# Power.net
KiCad netlist of a schematic drawn in Altium Designer
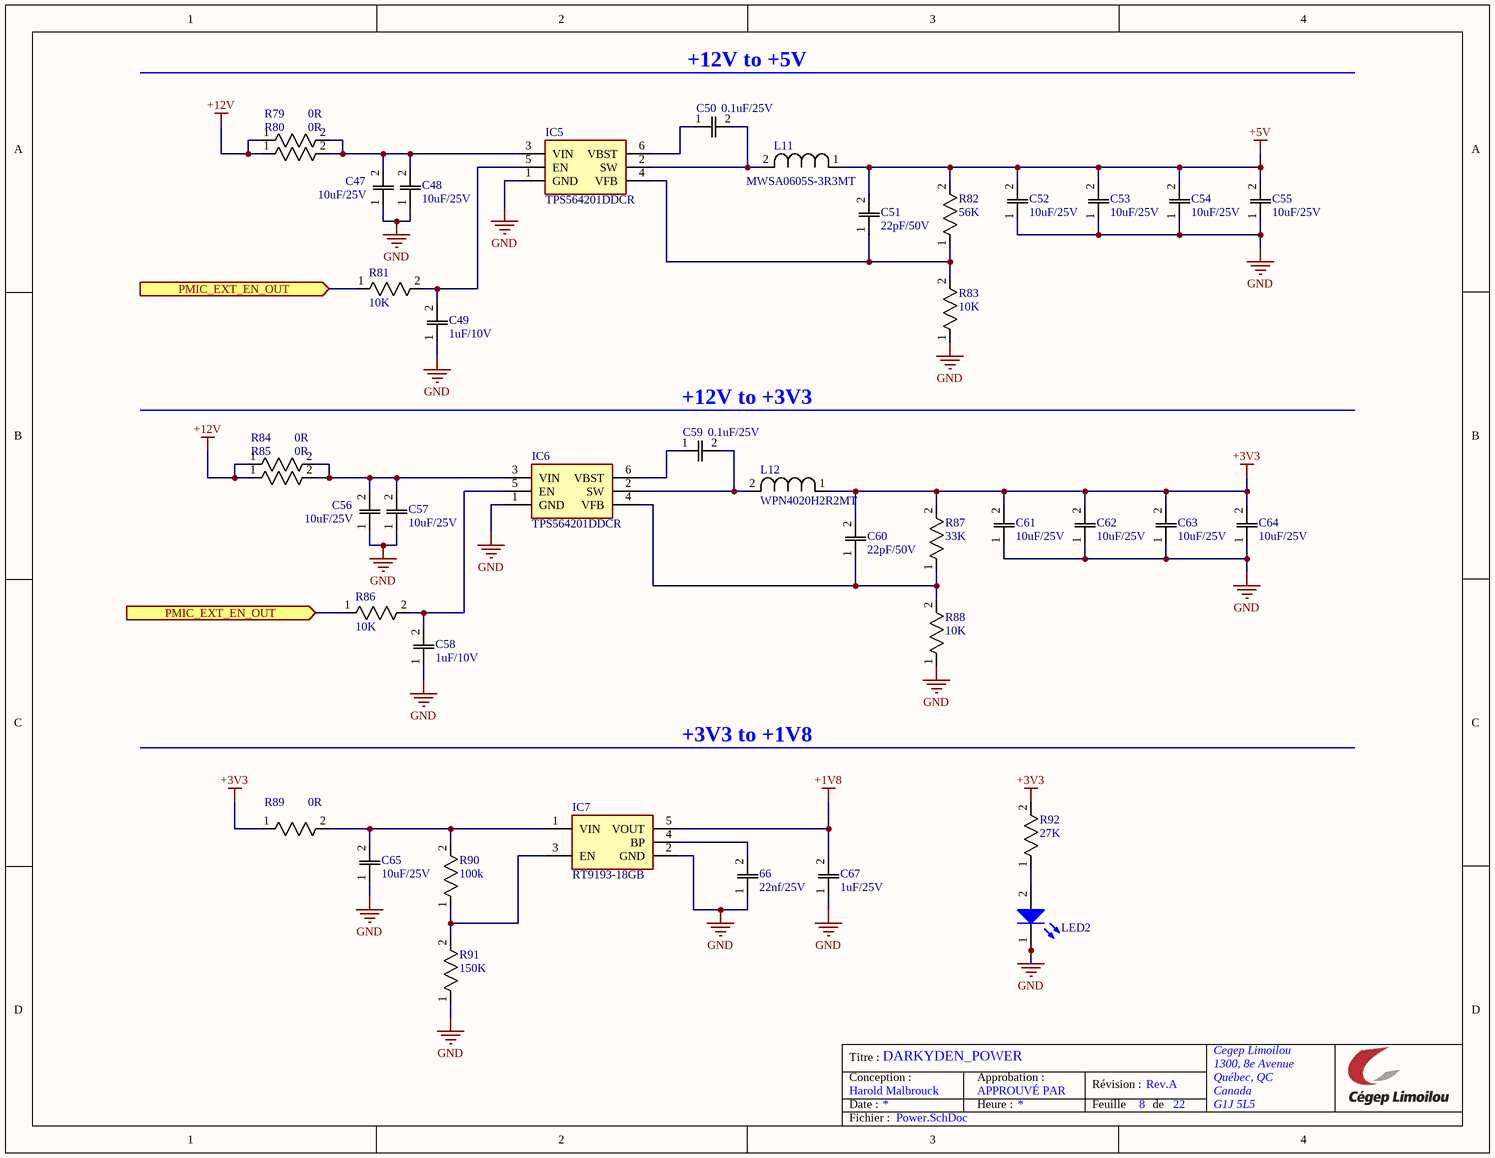
[diagram p0: Power.SchDoc]

(export (version "E")
  (design (tool "Eeschema 10.0.6"))
  (components
    (comp (ref "66")
      (value "22nf/25V")
      (footprint "SamacSys:C0805")
      (description "22nF, 25 V, 0805 [2012 Metric], 5%, C0G / NP0")
      (fields
        (field (name "MANUFACTURER_PART_NUMBER") "C0805C223J3GACTU")
        (field (name "MANUFACTURER") "KEMET")
      )
      (libsource (lib "SamacSys") (part "C0805C223J3GACTU"))
    )
    (comp (ref "C47")
      (value "10uF/25V")
      (footprint "CAPC220145_88N_KEM")
      (description "10uF / 25 VDC, +85degC, X5R Dielec, +/-10% ¦ KEMET C0805C106K3PACTU 0805")
      (fields
        (field (name "MANUFACTURER") "KEMET")
        (field (name "MANUFACTURER PART NUMBER") "C0805C106K3PACTU")
      )
      (libsource (lib "C0805C106K3PACTU") (part "C0805C106K3PACTU"))
    )
    (comp (ref "C48")
      (value "10uF/25V")
      (footprint "CAPC220145_88N_KEM")
      (description "10uF / 25 VDC, +85degC, X5R Dielec, +/-10% ¦ KEMET C0805C106K3PACTU 0805")
      (fields
        (field (name "MANUFACTURER") "KEMET")
        (field (name "MANUFACTURER PART NUMBER") "C0805C106K3PACTU")
      )
      (libsource (lib "C0805C106K3PACTU") (part "C0805C106K3PACTU"))
    )
    (comp (ref "C49")
      (value "1uF/10V")
      (footprint "CAPC220145_88N_KEM")
      (description "Multilayer Ceramic Capacitors MLCC - SMD/SMT 10V 1uF X7R 0805 10%")
      (fields
        (field (name "MANUFACTURER") "KEMET")
        (field (name "MANUFACTURER PART NUMBER") "C0805C105K8RACTU")
      )
      (libsource (lib "C0805C105K8RACTU") (part "C0805C105K8RACTU"))
    )
    (comp (ref "C50")
      (value "0.1uF/25V")
      (footprint "CAPC220145_88N_KEM")
      (description "0.1uF 25V X7R 10% SMD 0805 125C Plastic T/R")
      (fields
        (field (name "MANUFACTURER") "KEMET")
        (field (name "MANUFACTURER PART NUMBER") "C0805C104K3RACTU")
      )
      (libsource (lib "C0805C104K3RACTU") (part "C0805C104K3RACTU"))
    )
    (comp (ref "C51")
      (value "22pF/50V")
      (footprint "CAPC220145_88N_KEM")
      (description "Cap Ceramic 22pF 50V X7R 5% Pad SMD 0805 125°C T/R")
      (fields
        (field (name "MANUFACTURER") "KEMET")
        (field (name "MANUFACTURER PART NUMBER") "C0805C220J5RACTU")
      )
      (libsource (lib "C0805C220J5RACTU") (part "C0805C220J5RACTU"))
    )
    (comp (ref "C52")
      (value "10uF/25V")
      (footprint "CAPC220145_88N_KEM")
      (description "10uF / 25 VDC, +85degC, X5R Dielec, +/-10% ¦ KEMET C0805C106K3PACTU 0805")
      (fields
        (field (name "MANUFACTURER") "KEMET")
        (field (name "MANUFACTURER PART NUMBER") "C0805C106K3PACTU")
      )
      (libsource (lib "C0805C106K3PACTU") (part "C0805C106K3PACTU"))
    )
    (comp (ref "C53")
      (value "10uF/25V")
      (footprint "CAPC220145_88N_KEM")
      (description "10uF / 25 VDC, +85degC, X5R Dielec, +/-10% ¦ KEMET C0805C106K3PACTU 0805")
      (fields
        (field (name "MANUFACTURER") "KEMET")
        (field (name "MANUFACTURER PART NUMBER") "C0805C106K3PACTU")
      )
      (libsource (lib "C0805C106K3PACTU") (part "C0805C106K3PACTU"))
    )
    (comp (ref "C54")
      (value "10uF/25V")
      (footprint "CAPC220145_88N_KEM")
      (description "10uF / 25 VDC, +85degC, X5R Dielec, +/-10% ¦ KEMET C0805C106K3PACTU 0805")
      (fields
        (field (name "MANUFACTURER") "KEMET")
        (field (name "MANUFACTURER PART NUMBER") "C0805C106K3PACTU")
      )
      (libsource (lib "C0805C106K3PACTU") (part "C0805C106K3PACTU"))
    )
    (comp (ref "C55")
      (value "10uF/25V")
      (footprint "CAPC220145_88N_KEM")
      (description "10uF / 25 VDC, +85degC, X5R Dielec, +/-10% ¦ KEMET C0805C106K3PACTU 0805")
      (fields
        (field (name "MANUFACTURER") "KEMET")
        (field (name "MANUFACTURER PART NUMBER") "C0805C106K3PACTU")
      )
      (libsource (lib "C0805C106K3PACTU") (part "C0805C106K3PACTU"))
    )
    (comp (ref "C56")
      (value "10uF/25V")
      (footprint "CAPC220145_88N_KEM")
      (description "10uF / 25 VDC, +85degC, X5R Dielec, +/-10% ¦ KEMET C0805C106K3PACTU 0805")
      (fields
        (field (name "MANUFACTURER") "KEMET")
        (field (name "MANUFACTURER PART NUMBER") "C0805C106K3PACTU")
      )
      (libsource (lib "C0805C106K3PACTU") (part "C0805C106K3PACTU"))
    )
    (comp (ref "C57")
      (value "10uF/25V")
      (footprint "CAPC220145_88N_KEM")
      (description "10uF / 25 VDC, +85degC, X5R Dielec, +/-10% ¦ KEMET C0805C106K3PACTU 0805")
      (fields
        (field (name "MANUFACTURER") "KEMET")
        (field (name "MANUFACTURER PART NUMBER") "C0805C106K3PACTU")
      )
      (libsource (lib "C0805C106K3PACTU") (part "C0805C106K3PACTU"))
    )
    (comp (ref "C58")
      (value "1uF/10V")
      (footprint "CAPC220145_88N_KEM")
      (description "Multilayer Ceramic Capacitors MLCC - SMD/SMT 10V 1uF X7R 0805 10%")
      (fields
        (field (name "MANUFACTURER") "KEMET")
        (field (name "MANUFACTURER PART NUMBER") "C0805C105K8RACTU")
      )
      (libsource (lib "C0805C105K8RACTU") (part "C0805C105K8RACTU"))
    )
    (comp (ref "C59")
      (value "0.1uF/25V")
      (footprint "CAPC220145_88N_KEM")
      (description "0.1uF 25V X7R 10% SMD 0805 125C Plastic T/R")
      (fields
        (field (name "MANUFACTURER") "KEMET")
        (field (name "MANUFACTURER PART NUMBER") "C0805C104K3RACTU")
      )
      (libsource (lib "C0805C104K3RACTU") (part "C0805C104K3RACTU"))
    )
    (comp (ref "C60")
      (value "22pF/50V")
      (footprint "CAPC220145_88N_KEM")
      (description "Cap Ceramic 22pF 50V X7R 5% Pad SMD 0805 125°C T/R")
      (fields
        (field (name "MANUFACTURER") "KEMET")
        (field (name "MANUFACTURER PART NUMBER") "C0805C220J5RACTU")
      )
      (libsource (lib "C0805C220J5RACTU") (part "C0805C220J5RACTU"))
    )
    (comp (ref "C61")
      (value "10uF/25V")
      (footprint "CAPC220145_88N_KEM")
      (description "10uF / 25 VDC, +85degC, X5R Dielec, +/-10% ¦ KEMET C0805C106K3PACTU 0805")
      (fields
        (field (name "MANUFACTURER") "KEMET")
        (field (name "MANUFACTURER PART NUMBER") "C0805C106K3PACTU")
      )
      (libsource (lib "C0805C106K3PACTU") (part "C0805C106K3PACTU"))
    )
    (comp (ref "C62")
      (value "10uF/25V")
      (footprint "CAPC220145_88N_KEM")
      (description "10uF / 25 VDC, +85degC, X5R Dielec, +/-10% ¦ KEMET C0805C106K3PACTU 0805")
      (fields
        (field (name "MANUFACTURER") "KEMET")
        (field (name "MANUFACTURER PART NUMBER") "C0805C106K3PACTU")
      )
      (libsource (lib "C0805C106K3PACTU") (part "C0805C106K3PACTU"))
    )
    (comp (ref "C63")
      (value "10uF/25V")
      (footprint "CAPC220145_88N_KEM")
      (description "10uF / 25 VDC, +85degC, X5R Dielec, +/-10% ¦ KEMET C0805C106K3PACTU 0805")
      (fields
        (field (name "MANUFACTURER") "KEMET")
        (field (name "MANUFACTURER PART NUMBER") "C0805C106K3PACTU")
      )
      (libsource (lib "C0805C106K3PACTU") (part "C0805C106K3PACTU"))
    )
    (comp (ref "C64")
      (value "10uF/25V")
      (footprint "CAPC220145_88N_KEM")
      (description "10uF / 25 VDC, +85degC, X5R Dielec, +/-10% ¦ KEMET C0805C106K3PACTU 0805")
      (fields
        (field (name "MANUFACTURER") "KEMET")
        (field (name "MANUFACTURER PART NUMBER") "C0805C106K3PACTU")
      )
      (libsource (lib "C0805C106K3PACTU") (part "C0805C106K3PACTU"))
    )
    (comp (ref "C65")
      (value "10uF/25V")
      (footprint "CAPC220145_88N_KEM")
      (description "10uF / 25 VDC, +85degC, X5R Dielec, +/-10% ¦ KEMET C0805C106K3PACTU 0805")
      (fields
        (field (name "MANUFACTURER") "KEMET")
        (field (name "MANUFACTURER PART NUMBER") "C0805C106K3PACTU")
      )
      (libsource (lib "C0805C106K3PACTU") (part "C0805C106K3PACTU"))
    )
    (comp (ref "C67")
      (value "1uF/25V")
      (footprint "SamacSys:C0805")
      (description "1 µF, 25 V (DC), ±10 %, SMD 0805, X7R, C0805C105K3RAC7800")
      (fields
        (field (name "MANUFACTURER_PART_NUMBER") "C0805C105K3RACTU")
        (field (name "MOUSER PART NUMBER") "80-C0805C105K3R")
      )
      (libsource (lib "SamacSys") (part "C0805C105K3RACTU"))
    )
    (comp (ref "IC5")
      (value "TPS564201DDCR")
      (footprint "SamacSys:SOT95P280X110-6N")
      (fields
        (field (name "MOUSER PART NUMBER") "595-TPS564201DDCR")
        (field (name "MANUFACTURER") "Texas Instruments")
      )
      (libsource (lib "SamacSys") (part "TPS564201DDCR"))
    )
    (comp (ref "IC6")
      (value "TPS564201DDCR")
      (footprint "SamacSys:SOT95P280X110-6N")
      (fields
        (field (name "MOUSER PART NUMBER") "595-TPS564201DDCR")
        (field (name "MANUFACTURER") "Texas Instruments")
      )
      (libsource (lib "SamacSys") (part "TPS564201DDCR"))
    )
    (comp (ref "IC7")
      (value "RT9193-18GB")
      (footprint "SamacSys:SOT94P279X130-5N")
      (description "Linear Voltage Regulator IC Positive Fixed 1.8V Output 300mA SOT-23-5")
      (fields (field (name "MOUSER PART NUMBER") "835-RT9193-18GB"))
      (libsource (lib "SamacSys") (part "RT9193-18GB"))
    )
    (comp (ref "L11")
      (value "MWSA0605S-3R3MT")
      (footprint "IND_MWSA0603S_SNL")
      (description "3.3 µH Shielded Drum Core, Wirewound Inductor 8.5 A 22mOhm Max Nonstandard")
      (libsource (lib "MWSA0603S-XRXMT") (part "MWSA0605S-3R3MT"))
    )
    (comp (ref "L12")
      (value "WPN4020H2R2MT")
      (footprint "IND_WPN4020H_SNL")
      (description "2.2 µH Shielded Drum Core, Wirewound Inductor 4.3 A 48mOhm Max Nonstandard")
      (fields (field (name "MANUFACTURER") "Sunlord"))
      (libsource (lib "WPN4020H2R2MT") (part "WPN4020H2R2MT"))
    )
    (comp (ref "LED2")
      (value "Blue, 3.2V, 140°")
      (footprint "WL-SMCD_0603")
      (description "WL-SMCD Mono-color Chip LED Diffused, SMT, size 0603, Blue, 3.2V, 140°")
      (fields
        (field (name "MANUFACTURER PART NUMBER") "150060BS55040")
        (field (name "MANUFACTURER") "Wurth Elektronik")
      )
      (libsource (lib "0603_LED") (part "BLUE"))
    )
    (comp (ref "R79")
      (value "0R")
      (footprint "SamacSys:ERJ3EKF1000V")
      (description "Zero Ohm Resistor, Jumper, 0603 [1608 Metric], Thick Film, 100 mW, 1 A, Surface Mount")
      (fields
        (field (name "MANUFACTURER_PART_NUMBER") "ERJ-3GEY0R00V")
        (field (name "MOUSER PART NUMBER") "667-ERJ-3GEY0R00V")
      )
      (libsource (lib "SamacSys") (part "ERJ-3GEY0R00V"))
    )
    (comp (ref "R80")
      (value "0R")
      (footprint "SamacSys:ERJ3EKF1000V")
      (description "Zero Ohm Resistor, Jumper, 0603 [1608 Metric], Thick Film, 100 mW, 1 A, Surface Mount")
      (fields
        (field (name "MANUFACTURER_PART_NUMBER") "ERJ-3GEY0R00V")
        (field (name "MOUSER PART NUMBER") "667-ERJ-3GEY0R00V")
      )
      (libsource (lib "SamacSys") (part "ERJ-3GEY0R00V"))
    )
    (comp (ref "R81")
      (value "10K")
      (footprint "SamacSys:ERJ3EKF1000V")
      (description "10K Ohm 5% Res Thick Film 0603  0.1W(1/10W) ±200ppm/C Pad SMD Automotive T/R")
      (fields
        (field (name "MANUFACTURER_PART_NUMBER") "ERJ-3GEYJ103V")
        (field (name "MOUSER PART NUMBER") "667-ERJ-3GEYJ103V")
      )
      (libsource (lib "SamacSys") (part "ERJ-3GEYJ103V"))
    )
    (comp (ref "R82")
      (value "56K")
      (footprint "SamacSys:RESC1608X55N")
      (description "56K Ohm 1% 1/10W +/-100ppm/ßC Molded SMD Punched Carrier T/R")
      (fields
        (field (name "MANUFACTURER_PART_NUMBER") "ERJ-3EKF5602V")
        (field (name "MOUSER PART NUMBER") "667-ERJ-3EKF5602V")
      )
      (libsource (lib "SamacSys") (part "ERJ-3EKF5602V"))
    )
    (comp (ref "R83")
      (value "10K")
      (footprint "SamacSys:ERJ3EKF1000V")
      (description "10K Ohm 5% Res Thick Film 0603  0.1W(1/10W) ±200ppm/C Pad SMD Automotive T/R")
      (fields
        (field (name "MANUFACTURER_PART_NUMBER") "ERJ-3GEYJ103V")
        (field (name "MOUSER PART NUMBER") "667-ERJ-3GEYJ103V")
      )
      (libsource (lib "SamacSys") (part "ERJ-3GEYJ103V"))
    )
    (comp (ref "R84")
      (value "0R")
      (footprint "SamacSys:ERJ3EKF1000V")
      (description "Zero Ohm Resistor, Jumper, 0603 [1608 Metric], Thick Film, 100 mW, 1 A, Surface Mount")
      (fields
        (field (name "MANUFACTURER_PART_NUMBER") "ERJ-3GEY0R00V")
        (field (name "MOUSER PART NUMBER") "667-ERJ-3GEY0R00V")
      )
      (libsource (lib "SamacSys") (part "ERJ-3GEY0R00V"))
    )
    (comp (ref "R85")
      (value "0R")
      (footprint "SamacSys:ERJ3EKF1000V")
      (description "Zero Ohm Resistor, Jumper, 0603 [1608 Metric], Thick Film, 100 mW, 1 A, Surface Mount")
      (fields
        (field (name "MANUFACTURER_PART_NUMBER") "ERJ-3GEY0R00V")
        (field (name "MOUSER PART NUMBER") "667-ERJ-3GEY0R00V")
      )
      (libsource (lib "SamacSys") (part "ERJ-3GEY0R00V"))
    )
    (comp (ref "R86")
      (value "10K")
      (footprint "SamacSys:ERJ3EKF1000V")
      (description "10K Ohm 5% Res Thick Film 0603  0.1W(1/10W) ±200ppm/C Pad SMD Automotive T/R")
      (fields
        (field (name "MANUFACTURER_PART_NUMBER") "ERJ-3GEYJ103V")
        (field (name "MOUSER PART NUMBER") "667-ERJ-3GEYJ103V")
      )
      (libsource (lib "SamacSys") (part "ERJ-3GEYJ103V"))
    )
    (comp (ref "R87")
      (value "33K")
      (footprint "SamacSys:ERJ3EKF1000V")
      (description "33K Ohm 0603  5% 0.1W(1/10W) +/-200ppm/ßC SMD Automotive T/R")
      (fields
        (field (name "MANUFACTURER_PART_NUMBER") "ERJ-3GEYJ333V")
        (field (name "MOUSER PART NUMBER") "667-ERJ-3GEYJ333V")
      )
      (libsource (lib "SamacSys") (part "ERJ-3GEYJ333V"))
    )
    (comp (ref "R88")
      (value "10K")
      (footprint "SamacSys:ERJ3EKF1000V")
      (description "10K Ohm 5% Res Thick Film 0603  0.1W(1/10W) ±200ppm/C Pad SMD Automotive T/R")
      (fields
        (field (name "MANUFACTURER_PART_NUMBER") "ERJ-3GEYJ103V")
        (field (name "MOUSER PART NUMBER") "667-ERJ-3GEYJ103V")
      )
      (libsource (lib "SamacSys") (part "ERJ-3GEYJ103V"))
    )
    (comp (ref "R89")
      (value "0R")
      (footprint "SamacSys:ERJ3EKF1000V")
      (description "Zero Ohm Resistor, Jumper, 0603 [1608 Metric], Thick Film, 100 mW, 1 A, Surface Mount")
      (fields
        (field (name "MANUFACTURER_PART_NUMBER") "ERJ-3GEY0R00V")
        (field (name "MOUSER PART NUMBER") "667-ERJ-3GEY0R00V")
      )
      (libsource (lib "SamacSys") (part "ERJ-3GEY0R00V"))
    )
    (comp (ref "R90")
      (value "100k")
      (footprint "SamacSys:ERJ3EKF1000V")
      (description "100K Ohm 5%  Res Thick Film 0603 1/10W +/-200ppm/ßC Molded SMD Punched Carrier T/R")
      (fields
        (field (name "MANUFACTURER_PART_NUMBER") "ERJ-3GEYJ104V")
        (field (name "MOUSER PART NUMBER") "667-ERJ-3GEYJ104V")
      )
      (libsource (lib "SamacSys") (part "ERJ-3GEYJ104V"))
    )
    (comp (ref "R91")
      (value "150K")
      (footprint "SamacSys:ERJ3EKF1000V")
      (description "150 kOhm, ± 5%, 100 mW, 0603 [1608 Metric], Thick Film, General Purpose")
      (fields
        (field (name "MANUFACTURER_PART_NUMBER") "ERJ-3GEYJ154V")
        (field (name "MOUSER PART NUMBER") "667-ERJ-3GEYJ154V")
      )
      (libsource (lib "SamacSys") (part "ERJ-3GEYJ154V"))
    )
    (comp (ref "R92")
      (value "27K")
      (footprint "RC0603N_PAN")
      (description "Res Thick Film 0603 27K Ohm 1% 1/10W ±100ppm/°C Molded SMD Punched Carrier T/R")
      (fields
        (field (name "MANUFACTURER") "Panasonic")
        (field (name "MANUFACTURER PART NUMBER") "ERJ-3EKF2702V")
      )
      (libsource (lib "ERJ-3EKF2702V") (part "ERJ-3EKF2702V"))
    )
  )
  (nets
    (net (code "1") (name "+1V8") (class "Default")
      (node (ref "C67") (pin "2") (pinfunction "2_2") (pintype "passive"))
      (node (ref "IC7") (pin "5") (pinfunction "VOUT_5") (pintype "passive"))
    )
    (net (code "2") (name "+3V3") (class "Default")
      (node (ref "C60") (pin "2") (pinfunction "2_2") (pintype "passive"))
      (node (ref "C61") (pin "2") (pinfunction "2_2") (pintype "passive"))
      (node (ref "C62") (pin "2") (pinfunction "2_2") (pintype "passive"))
      (node (ref "C63") (pin "2") (pinfunction "2_2") (pintype "passive"))
      (node (ref "C64") (pin "2") (pinfunction "2_2") (pintype "passive"))
      (node (ref "L12") (pin "1") (pinfunction "1_1") (pintype "passive"))
      (node (ref "R87") (pin "2") (pinfunction "2_2") (pintype "passive"))
      (node (ref "R89") (pin "1") (pinfunction "1_1") (pintype "passive"))
      (node (ref "R92") (pin "2") (pinfunction "2_2") (pintype "passive"))
    )
    (net (code "3") (name "+5V") (class "Default")
      (node (ref "C51") (pin "2") (pinfunction "2_2") (pintype "passive"))
      (node (ref "C52") (pin "2") (pinfunction "2_2") (pintype "passive"))
      (node (ref "C53") (pin "2") (pinfunction "2_2") (pintype "passive"))
      (node (ref "C54") (pin "2") (pinfunction "2_2") (pintype "passive"))
      (node (ref "C55") (pin "2") (pinfunction "2_2") (pintype "passive"))
      (node (ref "L11") (pin "1") (pinfunction "1_1") (pintype "passive"))
      (node (ref "R82") (pin "2") (pinfunction "2_2") (pintype "passive"))
    )
    (net (code "4") (name "+12V") (class "Default")
      (node (ref "R79") (pin "1") (pinfunction "1_1") (pintype "passive"))
      (node (ref "R80") (pin "1") (pinfunction "1_1") (pintype "passive"))
      (node (ref "R84") (pin "1") (pinfunction "1_1") (pintype "passive"))
      (node (ref "R85") (pin "1") (pinfunction "1_1") (pintype "passive"))
    )
    (net (code "5") (name "/PMIC_EXT_EN_OUT") (class "Default")
      (node (ref "R81") (pin "1") (pinfunction "1_1") (pintype "passive"))
      (node (ref "R86") (pin "1") (pinfunction "1_1") (pintype "passive"))
    )
    (net (code "6") (name "GND") (class "Default")
      (node (ref "66") (pin "1") (pinfunction "1_1") (pintype "passive"))
      (node (ref "C47") (pin "1") (pinfunction "1_1") (pintype "passive"))
      (node (ref "C48") (pin "1") (pinfunction "1_1") (pintype "passive"))
      (node (ref "C49") (pin "1") (pinfunction "1_1") (pintype "passive"))
      (node (ref "C52") (pin "1") (pinfunction "1_1") (pintype "passive"))
      (node (ref "C53") (pin "1") (pinfunction "1_1") (pintype "passive"))
      (node (ref "C54") (pin "1") (pinfunction "1_1") (pintype "passive"))
      (node (ref "C55") (pin "1") (pinfunction "1_1") (pintype "passive"))
      (node (ref "C56") (pin "1") (pinfunction "1_1") (pintype "passive"))
      (node (ref "C57") (pin "1") (pinfunction "1_1") (pintype "passive"))
      (node (ref "C58") (pin "1") (pinfunction "1_1") (pintype "passive"))
      (node (ref "C61") (pin "1") (pinfunction "1_1") (pintype "passive"))
      (node (ref "C62") (pin "1") (pinfunction "1_1") (pintype "passive"))
      (node (ref "C63") (pin "1") (pinfunction "1_1") (pintype "passive"))
      (node (ref "C64") (pin "1") (pinfunction "1_1") (pintype "passive"))
      (node (ref "C65") (pin "1") (pinfunction "1_1") (pintype "passive"))
      (node (ref "C67") (pin "1") (pinfunction "1_1") (pintype "passive"))
      (node (ref "IC5") (pin "1") (pinfunction "GND_1") (pintype "passive"))
      (node (ref "IC6") (pin "1") (pinfunction "GND_1") (pintype "passive"))
      (node (ref "IC7") (pin "2") (pinfunction "GND_2") (pintype "passive"))
      (node (ref "LED2") (pin "1") (pinfunction "K_1") (pintype "passive"))
      (node (ref "R83") (pin "1") (pinfunction "1_1") (pintype "passive"))
      (node (ref "R88") (pin "1") (pinfunction "1_1") (pintype "passive"))
      (node (ref "R91") (pin "1") (pinfunction "1_1") (pintype "passive"))
    )
    (net (code "7") (name "Net-(IC5-EN)") (class "Default")
      (node (ref "C49") (pin "2") (pinfunction "2_2") (pintype "passive"))
      (node (ref "IC5") (pin "5") (pinfunction "EN_5") (pintype "passive"))
      (node (ref "R81") (pin "2") (pinfunction "2_2") (pintype "passive"))
    )
    (net (code "8") (name "Net-(IC5-SW)") (class "Default")
      (node (ref "C50") (pin "2") (pinfunction "2_2") (pintype "passive"))
      (node (ref "IC5") (pin "2") (pinfunction "SW_2") (pintype "passive"))
      (node (ref "L11") (pin "2") (pinfunction "2_2") (pintype "passive"))
    )
    (net (code "9") (name "Net-(IC5-VBST)") (class "Default")
      (node (ref "C50") (pin "1") (pinfunction "1_1") (pintype "passive"))
      (node (ref "IC5") (pin "6") (pinfunction "VBST_6") (pintype "passive"))
    )
    (net (code "10") (name "Net-(IC5-VFB)") (class "Default")
      (node (ref "C51") (pin "1") (pinfunction "1_1") (pintype "passive"))
      (node (ref "IC5") (pin "4") (pinfunction "VFB_4") (pintype "passive"))
      (node (ref "R82") (pin "1") (pinfunction "1_1") (pintype "passive"))
      (node (ref "R83") (pin "2") (pinfunction "2_2") (pintype "passive"))
    )
    (net (code "11") (name "Net-(IC5-VIN)") (class "Default")
      (node (ref "C47") (pin "2") (pinfunction "2_2") (pintype "passive"))
      (node (ref "C48") (pin "2") (pinfunction "2_2") (pintype "passive"))
      (node (ref "IC5") (pin "3") (pinfunction "VIN_3") (pintype "passive"))
      (node (ref "R79") (pin "2") (pinfunction "2_2") (pintype "passive"))
      (node (ref "R80") (pin "2") (pinfunction "2_2") (pintype "passive"))
    )
    (net (code "12") (name "Net-(IC6-EN)") (class "Default")
      (node (ref "C58") (pin "2") (pinfunction "2_2") (pintype "passive"))
      (node (ref "IC6") (pin "5") (pinfunction "EN_5") (pintype "passive"))
      (node (ref "R86") (pin "2") (pinfunction "2_2") (pintype "passive"))
    )
    (net (code "13") (name "Net-(IC6-SW)") (class "Default")
      (node (ref "C59") (pin "2") (pinfunction "2_2") (pintype "passive"))
      (node (ref "IC6") (pin "2") (pinfunction "SW_2") (pintype "passive"))
      (node (ref "L12") (pin "2") (pinfunction "2_2") (pintype "passive"))
    )
    (net (code "14") (name "Net-(IC6-VBST)") (class "Default")
      (node (ref "C59") (pin "1") (pinfunction "1_1") (pintype "passive"))
      (node (ref "IC6") (pin "6") (pinfunction "VBST_6") (pintype "passive"))
    )
    (net (code "15") (name "Net-(IC6-VFB)") (class "Default")
      (node (ref "C60") (pin "1") (pinfunction "1_1") (pintype "passive"))
      (node (ref "IC6") (pin "4") (pinfunction "VFB_4") (pintype "passive"))
      (node (ref "R87") (pin "1") (pinfunction "1_1") (pintype "passive"))
      (node (ref "R88") (pin "2") (pinfunction "2_2") (pintype "passive"))
    )
    (net (code "16") (name "Net-(IC6-VIN)") (class "Default")
      (node (ref "C56") (pin "2") (pinfunction "2_2") (pintype "passive"))
      (node (ref "C57") (pin "2") (pinfunction "2_2") (pintype "passive"))
      (node (ref "IC6") (pin "3") (pinfunction "VIN_3") (pintype "passive"))
      (node (ref "R84") (pin "2") (pinfunction "2_2") (pintype "passive"))
      (node (ref "R85") (pin "2") (pinfunction "2_2") (pintype "passive"))
    )
    (net (code "17") (name "Net-(IC7-BP)") (class "Default")
      (node (ref "66") (pin "2") (pinfunction "2_2") (pintype "passive"))
      (node (ref "IC7") (pin "4") (pinfunction "BP_4") (pintype "passive"))
    )
    (net (code "18") (name "Net-(IC7-EN)") (class "Default")
      (node (ref "IC7") (pin "3") (pinfunction "EN_3") (pintype "passive"))
      (node (ref "R90") (pin "1") (pinfunction "1_1") (pintype "passive"))
      (node (ref "R91") (pin "2") (pinfunction "2_2") (pintype "passive"))
    )
    (net (code "19") (name "Net-(IC7-VIN)") (class "Default")
      (node (ref "C65") (pin "2") (pinfunction "2_2") (pintype "passive"))
      (node (ref "IC7") (pin "1") (pinfunction "VIN_1") (pintype "passive"))
      (node (ref "R89") (pin "2") (pinfunction "2_2") (pintype "passive"))
      (node (ref "R90") (pin "2") (pinfunction "2_2") (pintype "passive"))
    )
    (net (code "20") (name "Net-(LED2-A)") (class "Default")
      (node (ref "LED2") (pin "2") (pinfunction "A_2") (pintype "passive"))
      (node (ref "R92") (pin "1") (pinfunction "1_1") (pintype "passive"))
    )
  )
)
